# Sensor_LM35_Package.net
KiCad netlist of a schematic drawn in Altium Designer
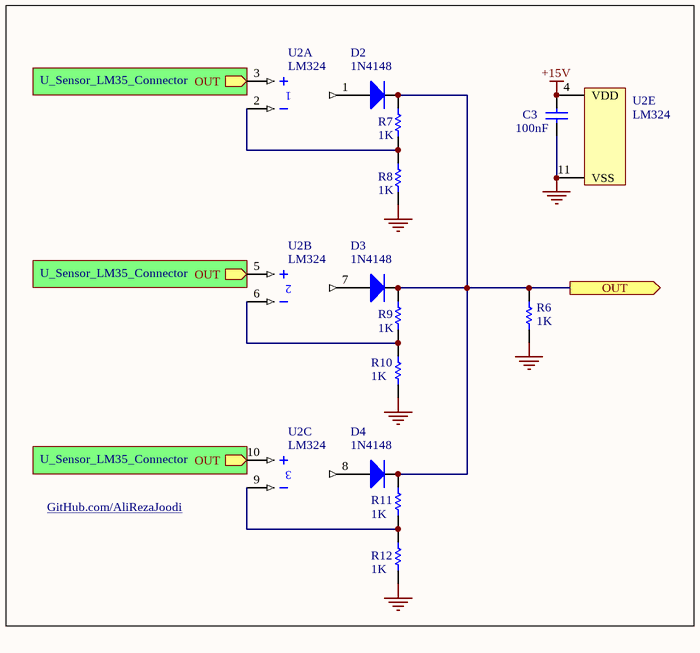
[diagram p0: Sensor_LM35_Package.SchDoc]

(export (version "E")
  (design (tool "Eeschema 10.0.6"))
  (components
    (comp (ref "C3")
      (value "100nF")
      (footprint "CAPNTO2.54-3.05x1.78A")
      (description "Capacitor")
      (fields (field (name "MANUFACTURER") "Generic Components") (field (name "PUBLISHER") "Altium Limited"))
      (libsource (lib "Miscellaneous Devices") (part "Cap"))
    )
    (comp (ref "D2")
      (value "1N4148")
      (footprint "DIODE0.4_Glass")
      (description "Default Diode")
      (fields (field (name "MANUFACTURER") "Generic Components") (field (name "PUBLISHER") "Altium Limited"))
      (libsource (lib "Miscellaneous Devices") (part "Diode"))
    )
    (comp (ref "D3")
      (value "1N4148")
      (footprint "DIODE0.4_Glass")
      (description "Default Diode")
      (fields (field (name "MANUFACTURER") "Generic Components") (field (name "PUBLISHER") "Altium Limited"))
      (libsource (lib "Miscellaneous Devices") (part "Diode"))
    )
    (comp (ref "D4")
      (value "1N4148")
      (footprint "DIODE0.4_Glass")
      (description "Default Diode")
      (fields (field (name "MANUFACTURER") "Generic Components") (field (name "PUBLISHER") "Altium Limited"))
      (libsource (lib "Miscellaneous Devices") (part "Diode"))
    )
    (comp (ref "R6")
      (value "1K")
      (footprint "AXIAL-0.4")
      (description "Resistor")
      (fields (field (name "PUBLISHER") "Altium Limited"))
      (libsource (lib "Miscellaneous Devices") (part "Res1"))
    )
    (comp (ref "R7")
      (value "1K")
      (footprint "AXIAL-0.4")
      (description "Resistor")
      (fields (field (name "PUBLISHER") "Altium Limited"))
      (libsource (lib "Miscellaneous Devices") (part "Res1"))
    )
    (comp (ref "R8")
      (value "1K")
      (footprint "AXIAL-0.4")
      (description "Resistor")
      (fields (field (name "PUBLISHER") "Altium Limited"))
      (libsource (lib "Miscellaneous Devices") (part "Res1"))
    )
    (comp (ref "R9")
      (value "1K")
      (footprint "AXIAL-0.4")
      (description "Resistor")
      (fields (field (name "PUBLISHER") "Altium Limited"))
      (libsource (lib "Miscellaneous Devices") (part "Res1"))
    )
    (comp (ref "R10")
      (value "1K")
      (footprint "AXIAL-0.4")
      (description "Resistor")
      (fields (field (name "PUBLISHER") "Altium Limited"))
      (libsource (lib "Miscellaneous Devices") (part "Res1"))
    )
    (comp (ref "R11")
      (value "1K")
      (footprint "AXIAL-0.4")
      (description "Resistor")
      (fields (field (name "PUBLISHER") "Altium Limited"))
      (libsource (lib "Miscellaneous Devices") (part "Res1"))
    )
    (comp (ref "R12")
      (value "1K")
      (footprint "AXIAL-0.4")
      (description "Resistor")
      (fields (field (name "PUBLISHER") "Altium Limited"))
      (libsource (lib "Miscellaneous Devices") (part "Res1"))
    )
    (comp (ref "U2")
      (value "LM324")
      (footprint "646-06")
      (description "Quad Low-Power Operational Amplifier")
      (fields (field (name "PUBLISHER") "Altium Limited"))
      (libsource (lib "my Libraries") (part "LM324"))
    )
  )
  (nets
    (net (code "1") (name "+15V") (class "Default")
      (node (ref "C3") (pin "2") (pinfunction "2_2") (pintype "passive"))
      (node (ref "U2") (pin "4") (pinfunction "VDD_4") (pintype "passive"))
    )
    (net (code "2") (name "/OUT") (class "Default")
      (node (ref "D2") (pin "2") (pinfunction "K_2") (pintype "passive"))
      (node (ref "D3") (pin "2") (pinfunction "K_2") (pintype "passive"))
      (node (ref "D4") (pin "2") (pinfunction "K_2") (pintype "passive"))
      (node (ref "R11") (pin "2") (pinfunction "2_2") (pintype "passive"))
      (node (ref "R6") (pin "1") (pinfunction "1_1") (pintype "passive"))
      (node (ref "R7") (pin "2") (pinfunction "2_2") (pintype "passive"))
      (node (ref "R9") (pin "2") (pinfunction "2_2") (pintype "passive"))
    )
    (net (code "3") (name "/OUT_1") (class "Default")
      (node (ref "U2") (pin "10") (pinfunction "IN+_10") (pintype "input"))
    )
    (net (code "4") (name "/OUT_2") (class "Default")
      (node (ref "U2") (pin "5") (pinfunction "IN+_5") (pintype "input"))
    )
    (net (code "5") (name "/OUT_3") (class "Default")
      (node (ref "U2") (pin "3") (pinfunction "IN+_3") (pintype "input"))
    )
    (net (code "6") (name "GND") (class "Default")
      (node (ref "C3") (pin "1") (pinfunction "1_1") (pintype "passive"))
      (node (ref "R10") (pin "1") (pinfunction "1_1") (pintype "passive"))
      (node (ref "R12") (pin "1") (pinfunction "1_1") (pintype "passive"))
      (node (ref "R6") (pin "2") (pinfunction "2_2") (pintype "passive"))
      (node (ref "R8") (pin "1") (pinfunction "1_1") (pintype "passive"))
      (node (ref "U2") (pin "11") (pinfunction "VSS_11") (pintype "power_in"))
    )
    (net (code "7") (name "Net-(D2-A)") (class "Default")
      (node (ref "D2") (pin "1") (pinfunction "A_1") (pintype "passive"))
      (node (ref "U2") (pin "1") (pinfunction "OUT_1") (pintype "output"))
    )
    (net (code "8") (name "Net-(D3-A)") (class "Default")
      (node (ref "D3") (pin "1") (pinfunction "A_1") (pintype "passive"))
      (node (ref "U2") (pin "7") (pinfunction "OUT_7") (pintype "output"))
    )
    (net (code "9") (name "Net-(D4-A)") (class "Default")
      (node (ref "D4") (pin "1") (pinfunction "A_1") (pintype "passive"))
      (node (ref "U2") (pin "8") (pinfunction "OUT_8") (pintype "output"))
    )
    (net (code "10") (name "Net-(U2A-IN-)") (class "Default")
      (node (ref "R7") (pin "1") (pinfunction "1_1") (pintype "passive"))
      (node (ref "R8") (pin "2") (pinfunction "2_2") (pintype "passive"))
      (node (ref "U2") (pin "2") (pinfunction "IN-_2") (pintype "input"))
    )
    (net (code "11") (name "Net-(U2B-IN-)") (class "Default")
      (node (ref "R10") (pin "2") (pinfunction "2_2") (pintype "passive"))
      (node (ref "R9") (pin "1") (pinfunction "1_1") (pintype "passive"))
      (node (ref "U2") (pin "6") (pinfunction "IN-_6") (pintype "input"))
    )
    (net (code "12") (name "Net-(U2C-IN-)") (class "Default")
      (node (ref "R11") (pin "1") (pinfunction "1_1") (pintype "passive"))
      (node (ref "R12") (pin "2") (pinfunction "2_2") (pintype "passive"))
      (node (ref "U2") (pin "9") (pinfunction "IN-_9") (pintype "input"))
    )
  )
)
